# Clock-Divider-4040.net
KiCad netlist of a schematic drawn in EAGLE
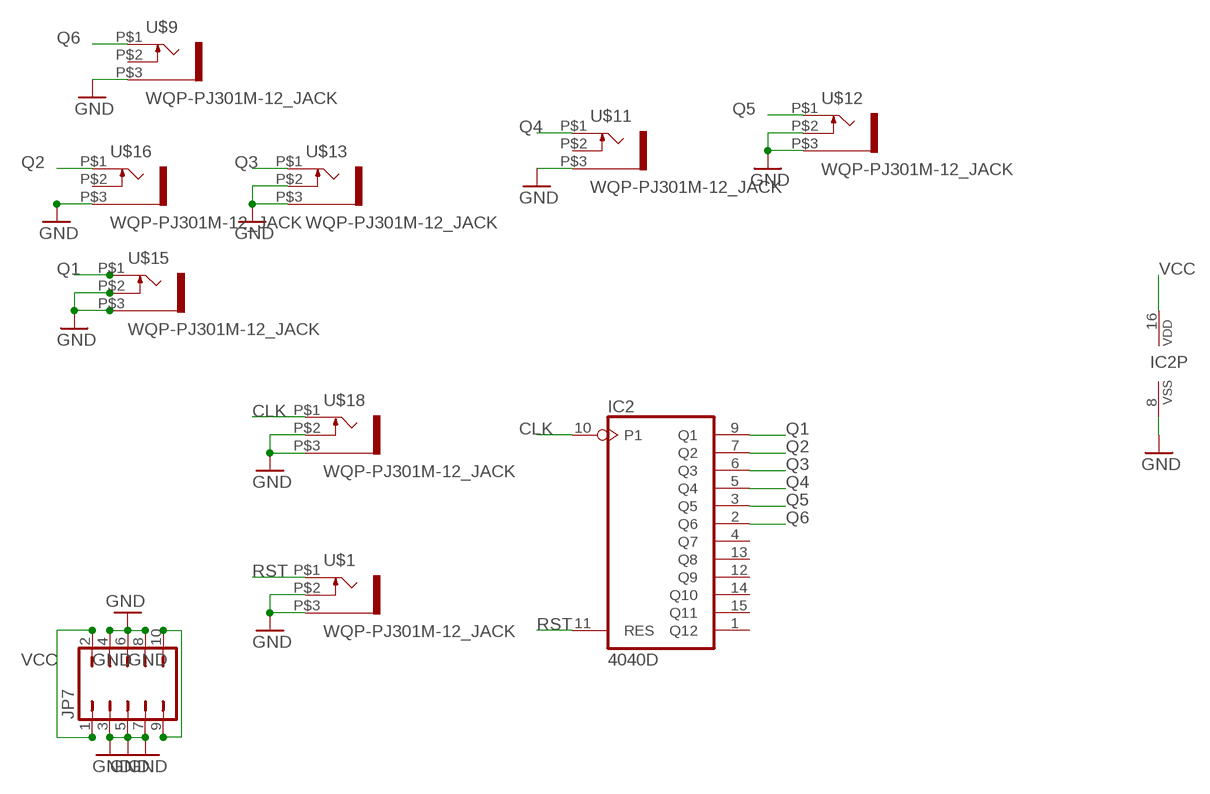
[diagram p0: schematic, sheet 1]

(export (version "E")
  (design (tool "Eeschema 10.0.6"))
  (components
    (comp (ref "IC2")
      (value "4040D")
      (footprint "eagle-import:SO16")
      (libsource (lib "eagle-import") (part "4040D"))
    )
    (comp (ref "JP7")
      (value "JP5Q")
      (footprint "eagle-import:JP5Q")
      (libsource (lib "eagle-import") (part "JP5Q"))
    )
    (comp (ref "U$1")
      (value "WQP-PJ301M-12_JACK")
      (footprint "eagle-import:WQP-PJ301M-12_JACK")
      (libsource (lib "eagle-import") (part "WQP-PJ301M-12_JACK"))
    )
    (comp (ref "U$9")
      (value "WQP-PJ301M-12_JACK")
      (footprint "eagle-import:WQP-PJ301M-12_JACK")
      (libsource (lib "eagle-import") (part "WQP-PJ301M-12_JACK"))
    )
    (comp (ref "U$11")
      (value "WQP-PJ301M-12_JACK")
      (footprint "eagle-import:WQP-PJ301M-12_JACK")
      (libsource (lib "eagle-import") (part "WQP-PJ301M-12_JACK"))
    )
    (comp (ref "U$12")
      (value "WQP-PJ301M-12_JACK")
      (footprint "eagle-import:WQP-PJ301M-12_JACK")
      (libsource (lib "eagle-import") (part "WQP-PJ301M-12_JACK"))
    )
    (comp (ref "U$13")
      (value "WQP-PJ301M-12_JACK")
      (footprint "eagle-import:WQP-PJ301M-12_JACK")
      (libsource (lib "eagle-import") (part "WQP-PJ301M-12_JACK"))
    )
    (comp (ref "U$15")
      (value "WQP-PJ301M-12_JACK")
      (footprint "eagle-import:WQP-PJ301M-12_JACK")
      (libsource (lib "eagle-import") (part "WQP-PJ301M-12_JACK"))
    )
    (comp (ref "U$16")
      (value "WQP-PJ301M-12_JACK")
      (footprint "eagle-import:WQP-PJ301M-12_JACK")
      (libsource (lib "eagle-import") (part "WQP-PJ301M-12_JACK"))
    )
    (comp (ref "U$18")
      (value "WQP-PJ301M-12_JACK")
      (footprint "eagle-import:WQP-PJ301M-12_JACK")
      (libsource (lib "eagle-import") (part "WQP-PJ301M-12_JACK"))
    )
  )
  (nets
    (net (code "1") (name "/CLK") (class "Default")
      (node (ref "IC2") (pin "10") (pinfunction "P1_10") (pintype "input"))
      (node (ref "U$18") (pin "P$1") (pinfunction "2_P$1") (pintype "passive"))
    )
    (net (code "2") (name "/Q1") (class "Default")
      (node (ref "IC2") (pin "9") (pinfunction "Q1_9") (pintype "output"))
      (node (ref "U$15") (pin "P$1") (pinfunction "2_P$1") (pintype "passive"))
    )
    (net (code "3") (name "/Q2") (class "Default")
      (node (ref "IC2") (pin "7") (pinfunction "Q2_7") (pintype "output"))
      (node (ref "U$16") (pin "P$1") (pinfunction "2_P$1") (pintype "passive"))
    )
    (net (code "4") (name "/Q3") (class "Default")
      (node (ref "IC2") (pin "6") (pinfunction "Q3_6") (pintype "output"))
      (node (ref "U$13") (pin "P$1") (pinfunction "2_P$1") (pintype "passive"))
    )
    (net (code "5") (name "/Q4") (class "Default")
      (node (ref "IC2") (pin "5") (pinfunction "Q4_5") (pintype "output"))
      (node (ref "U$11") (pin "P$1") (pinfunction "2_P$1") (pintype "passive"))
    )
    (net (code "6") (name "/Q5") (class "Default")
      (node (ref "IC2") (pin "3") (pinfunction "Q5_3") (pintype "output"))
      (node (ref "U$12") (pin "P$1") (pinfunction "2_P$1") (pintype "passive"))
    )
    (net (code "7") (name "/Q6") (class "Default")
      (node (ref "IC2") (pin "2") (pinfunction "Q6_2") (pintype "output"))
      (node (ref "U$9") (pin "P$1") (pinfunction "2_P$1") (pintype "passive"))
    )
    (net (code "8") (name "/RST") (class "Default")
      (node (ref "IC2") (pin "11") (pinfunction "RES_11") (pintype "input"))
      (node (ref "U$1") (pin "P$1") (pinfunction "2_P$1") (pintype "passive"))
    )
    (net (code "9") (name "/VCC") (class "Default")
      (node (ref "IC2") (pin "16") (pinfunction "VDD_16") (pintype "power_in"))
      (node (ref "JP7") (pin "1") (pinfunction "1_1") (pintype "passive"))
      (node (ref "JP7") (pin "2") (pinfunction "2_2") (pintype "passive"))
    )
    (net (code "10") (name "GND") (class "Default")
      (node (ref "IC2") (pin "8") (pinfunction "VSS_8") (pintype "power_in"))
      (node (ref "JP7") (pin "3") (pinfunction "3_3") (pintype "passive"))
      (node (ref "JP7") (pin "4") (pinfunction "4_4") (pintype "passive"))
      (node (ref "JP7") (pin "5") (pinfunction "5_5") (pintype "passive"))
      (node (ref "JP7") (pin "6") (pinfunction "6_6") (pintype "passive"))
      (node (ref "JP7") (pin "7") (pinfunction "7_7") (pintype "passive"))
      (node (ref "JP7") (pin "8") (pinfunction "8_8") (pintype "passive"))
      (node (ref "U$1") (pin "P$2") (pinfunction "3_P$2") (pintype "passive"))
      (node (ref "U$1") (pin "P$3") (pinfunction "1_P$3") (pintype "passive"))
      (node (ref "U$11") (pin "P$3") (pinfunction "1_P$3") (pintype "passive"))
      (node (ref "U$12") (pin "P$2") (pinfunction "3_P$2") (pintype "passive"))
      (node (ref "U$12") (pin "P$3") (pinfunction "1_P$3") (pintype "passive"))
      (node (ref "U$13") (pin "P$2") (pinfunction "3_P$2") (pintype "passive"))
      (node (ref "U$13") (pin "P$3") (pinfunction "1_P$3") (pintype "passive"))
      (node (ref "U$15") (pin "P$2") (pinfunction "3_P$2") (pintype "passive"))
      (node (ref "U$15") (pin "P$3") (pinfunction "1_P$3") (pintype "passive"))
      (node (ref "U$16") (pin "P$3") (pinfunction "1_P$3") (pintype "passive"))
      (node (ref "U$18") (pin "P$2") (pinfunction "3_P$2") (pintype "passive"))
      (node (ref "U$18") (pin "P$3") (pinfunction "1_P$3") (pintype "passive"))
      (node (ref "U$9") (pin "P$3") (pinfunction "1_P$3") (pintype "passive"))
    )
    (net (code "11") (name "Net-(JP7-Pad10)") (class "Default")
      (node (ref "JP7") (pin "10") (pinfunction "10_10") (pintype "passive"))
      (node (ref "JP7") (pin "9") (pinfunction "9_9") (pintype "passive"))
    )
    (net (code "12") (name "unconnected-(IC2A-Q7-Pad4)") (class "Default")
      (node (ref "IC2") (pin "4") (pinfunction "Q7_4") (pintype "output"))
    )
    (net (code "13") (name "unconnected-(IC2A-Q8-Pad13)") (class "Default")
      (node (ref "IC2") (pin "13") (pinfunction "Q8_13") (pintype "output"))
    )
    (net (code "14") (name "unconnected-(IC2A-Q9-Pad12)") (class "Default")
      (node (ref "IC2") (pin "12") (pinfunction "Q9_12") (pintype "output"))
    )
    (net (code "15") (name "unconnected-(IC2A-Q10-Pad14)") (class "Default")
      (node (ref "IC2") (pin "14") (pinfunction "Q10_14") (pintype "output"))
    )
    (net (code "16") (name "unconnected-(IC2A-Q11-Pad15)") (class "Default")
      (node (ref "IC2") (pin "15") (pinfunction "Q11_15") (pintype "output"))
    )
    (net (code "17") (name "unconnected-(IC2A-Q12-Pad1)") (class "Default")
      (node (ref "IC2") (pin "1") (pinfunction "Q12_1") (pintype "output"))
    )
    (net (code "18") (name "unconnected-(U$9-3-PadP$2)") (class "Default")
      (node (ref "U$9") (pin "P$2") (pinfunction "3_P$2") (pintype "passive"))
    )
    (net (code "19") (name "unconnected-(U$11-3-PadP$2)") (class "Default")
      (node (ref "U$11") (pin "P$2") (pinfunction "3_P$2") (pintype "passive"))
    )
    (net (code "20") (name "unconnected-(U$16-3-PadP$2)") (class "Default")
      (node (ref "U$16") (pin "P$2") (pinfunction "3_P$2") (pintype "passive"))
    )
  )
)
